# IO.net
KiCad netlist of a schematic drawn in Altium Designer
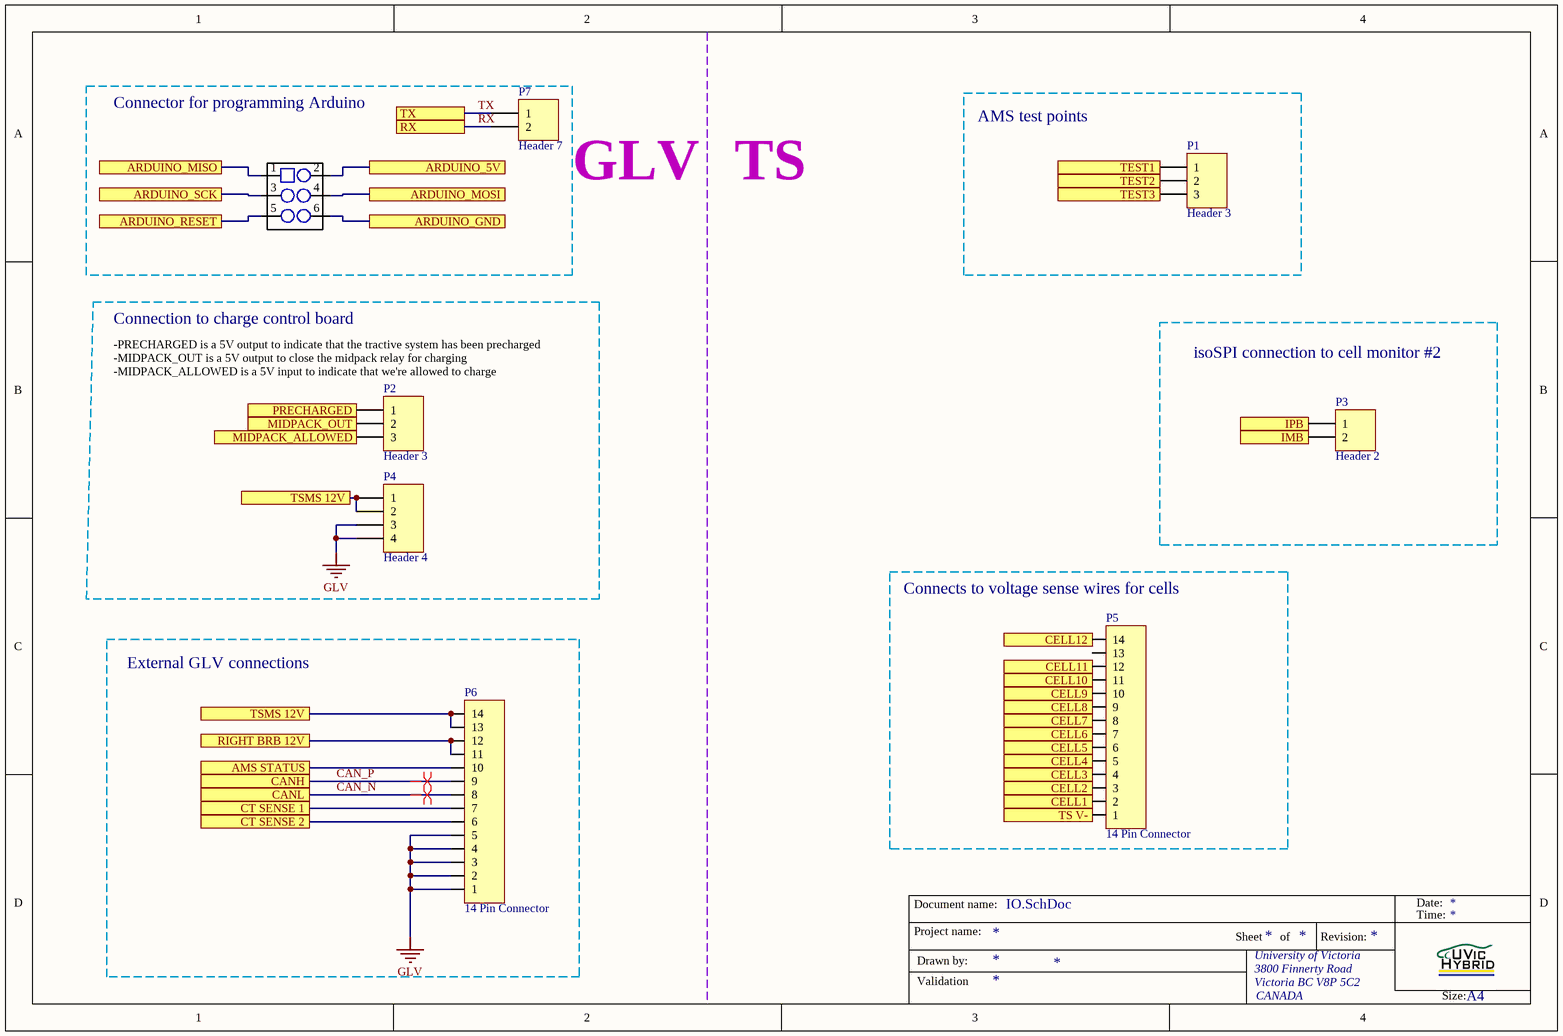
[diagram p0: IO.SchDoc]

(export (version "E")
  (design (tool "Eeschema 10.0.6"))
  (components
    (comp (ref "1")
      (value "ICSP Connector")
      (footprint "ICSP Connector")
      (libsource (lib "AMSComponents") (part "ICSP Connector"))
    )
    (comp (ref "P1")
      (value "Header 3")
      (footprint "3-pin Vertical nanofit")
      (description "Header, 3-Pin")
      (fields (field (name "PUBLISHER") "Altium Limited"))
      (libsource (lib "Miscellaneous Connectors") (part "Header 3"))
    )
    (comp (ref "P2")
      (value "Header 3")
      (footprint "3-pin Vertical nanofit")
      (description "Header, 3-Pin")
      (fields (field (name "PUBLISHER") "Altium Limited"))
      (libsource (lib "Miscellaneous Connectors") (part "Header 3"))
    )
    (comp (ref "P3")
      (value "Header 2")
      (footprint "2 Pin Nanofit")
      (description "Header, 2-Pin")
      (fields (field (name "PUBLISHER") "Altium Limited"))
      (libsource (lib "Miscellaneous Connectors") (part "Header 2"))
    )
    (comp (ref "P4")
      (value "Header 4")
      (footprint "4 Pin Vertical Nanofit")
      (description "Header, 4-Pin")
      (fields (field (name "PUBLISHER") "Altium Limited"))
      (libsource (lib "Miscellaneous Connectors") (part "Header 4"))
    )
    (comp (ref "P5")
      (value "14 Pin Connector")
      (footprint "TE Connectivity 14 Pin")
      (libsource (lib "AMSComponents") (part "14 Pin Connector"))
    )
    (comp (ref "P6")
      (value "14 Pin Connector")
      (footprint "TE Connectivity 14 Pin")
      (libsource (lib "AMSComponents") (part "14 Pin Connector"))
    )
    (comp (ref "P7")
      (value "Header 7")
      (footprint "2 Pin Nanofit")
      (description "Header, 2-Pin")
      (fields (field (name "PUBLISHER") "Altium Limited"))
      (libsource (lib "Miscellaneous Connectors") (part "Header 2"))
    )
  )
  (nets
    (net (code "1") (name "/AMS STATUS") (class "Default")
      (node (ref "P6") (pin "10") (pinfunction "10_10") (pintype "passive"))
    )
    (net (code "2") (name "/ARDUINO_5V") (class "Default")
      (node (ref "1") (pin "2") (pinfunction "2_2") (pintype "passive"))
    )
    (net (code "3") (name "/ARDUINO_GND") (class "Default")
      (node (ref "1") (pin "6") (pinfunction "6_6") (pintype "passive"))
    )
    (net (code "4") (name "/ARDUINO_MISO") (class "Default")
      (node (ref "1") (pin "1") (pinfunction "1_1") (pintype "passive"))
    )
    (net (code "5") (name "/ARDUINO_MOSI") (class "Default")
      (node (ref "1") (pin "4") (pinfunction "4_4") (pintype "passive"))
    )
    (net (code "6") (name "/ARDUINO_RESET") (class "Default")
      (node (ref "1") (pin "5") (pinfunction "5_5") (pintype "passive"))
    )
    (net (code "7") (name "/ARDUINO_SCK") (class "Default")
      (node (ref "1") (pin "3") (pinfunction "3_3") (pintype "passive"))
    )
    (net (code "8") (name "/CAN_N") (class "Default")
      (node (ref "P6") (pin "8") (pinfunction "8_8") (pintype "passive"))
    )
    (net (code "9") (name "/CAN_P") (class "Default")
      (node (ref "P6") (pin "9") (pinfunction "9_9") (pintype "passive"))
    )
    (net (code "10") (name "/CELL1") (class "Default")
      (node (ref "P5") (pin "2") (pinfunction "2_2") (pintype "passive"))
    )
    (net (code "11") (name "/CELL2") (class "Default")
      (node (ref "P5") (pin "3") (pinfunction "3_3") (pintype "passive"))
    )
    (net (code "12") (name "/CELL3") (class "Default")
      (node (ref "P5") (pin "4") (pinfunction "4_4") (pintype "passive"))
    )
    (net (code "13") (name "/CELL4") (class "Default")
      (node (ref "P5") (pin "5") (pinfunction "5_5") (pintype "passive"))
    )
    (net (code "14") (name "/CELL5") (class "Default")
      (node (ref "P5") (pin "6") (pinfunction "6_6") (pintype "passive"))
    )
    (net (code "15") (name "/CELL6") (class "Default")
      (node (ref "P5") (pin "7") (pinfunction "7_7") (pintype "passive"))
    )
    (net (code "16") (name "/CELL7") (class "Default")
      (node (ref "P5") (pin "8") (pinfunction "8_8") (pintype "passive"))
    )
    (net (code "17") (name "/CELL8") (class "Default")
      (node (ref "P5") (pin "9") (pinfunction "9_9") (pintype "passive"))
    )
    (net (code "18") (name "/CELL9") (class "Default")
      (node (ref "P5") (pin "10") (pinfunction "10_10") (pintype "passive"))
    )
    (net (code "19") (name "/CELL10") (class "Default")
      (node (ref "P5") (pin "11") (pinfunction "11_11") (pintype "passive"))
    )
    (net (code "20") (name "/CELL11") (class "Default")
      (node (ref "P5") (pin "12") (pinfunction "12_12") (pintype "passive"))
    )
    (net (code "21") (name "/CELL12") (class "Default")
      (node (ref "P5") (pin "14") (pinfunction "14_14") (pintype "passive"))
    )
    (net (code "22") (name "/CT SENSE 1") (class "Default")
      (node (ref "P6") (pin "7") (pinfunction "7_7") (pintype "passive"))
    )
    (net (code "23") (name "/CT SENSE 2") (class "Default")
      (node (ref "P6") (pin "6") (pinfunction "6_6") (pintype "passive"))
    )
    (net (code "24") (name "/IMB") (class "Default")
      (node (ref "P3") (pin "2") (pinfunction "2_2") (pintype "passive"))
    )
    (net (code "25") (name "/IPB") (class "Default")
      (node (ref "P3") (pin "1") (pinfunction "1_1") (pintype "passive"))
    )
    (net (code "26") (name "/MIDPACK_ALLOWED") (class "Default")
      (node (ref "P2") (pin "3") (pinfunction "3_3") (pintype "passive"))
    )
    (net (code "27") (name "/MIDPACK_OUT") (class "Default")
      (node (ref "P2") (pin "2") (pinfunction "2_2") (pintype "passive"))
    )
    (net (code "28") (name "/PRECHARGED") (class "Default")
      (node (ref "P2") (pin "1") (pinfunction "1_1") (pintype "passive"))
    )
    (net (code "29") (name "/RIGHT BRB 12V") (class "Default")
      (node (ref "P6") (pin "11") (pinfunction "11_11") (pintype "passive"))
      (node (ref "P6") (pin "12") (pinfunction "12_12") (pintype "passive"))
    )
    (net (code "30") (name "/RX") (class "Default")
      (node (ref "P7") (pin "2") (pinfunction "2_2") (pintype "passive"))
    )
    (net (code "31") (name "/TEST1") (class "Default")
      (node (ref "P1") (pin "1") (pinfunction "1_1") (pintype "passive"))
    )
    (net (code "32") (name "/TEST2") (class "Default")
      (node (ref "P1") (pin "2") (pinfunction "2_2") (pintype "passive"))
    )
    (net (code "33") (name "/TEST3") (class "Default")
      (node (ref "P1") (pin "3") (pinfunction "3_3") (pintype "passive"))
    )
    (net (code "34") (name "/TS V-") (class "Default")
      (node (ref "P5") (pin "1") (pinfunction "1_1") (pintype "passive"))
    )
    (net (code "35") (name "/TSMS 12V") (class "Default")
      (node (ref "P4") (pin "1") (pinfunction "1_1") (pintype "passive"))
      (node (ref "P4") (pin "2") (pinfunction "2_2") (pintype "passive"))
      (node (ref "P6") (pin "13") (pinfunction "13_13") (pintype "passive"))
      (node (ref "P6") (pin "14") (pinfunction "14_14") (pintype "passive"))
    )
    (net (code "36") (name "/TX") (class "Default")
      (node (ref "P7") (pin "1") (pinfunction "1_1") (pintype "passive"))
    )
    (net (code "37") (name "GLV") (class "Default")
      (node (ref "P4") (pin "3") (pinfunction "3_3") (pintype "passive"))
      (node (ref "P4") (pin "4") (pinfunction "4_4") (pintype "passive"))
      (node (ref "P6") (pin "1") (pinfunction "1_1") (pintype "passive"))
      (node (ref "P6") (pin "2") (pinfunction "2_2") (pintype "passive"))
      (node (ref "P6") (pin "3") (pinfunction "3_3") (pintype "passive"))
      (node (ref "P6") (pin "4") (pinfunction "4_4") (pintype "passive"))
      (node (ref "P6") (pin "5") (pinfunction "5_5") (pintype "passive"))
    )
    (net (code "38") (name "unconnected-(P5-Pad13)") (class "Default")
      (node (ref "P5") (pin "13") (pinfunction "13_13") (pintype "passive"))
    )
  )
)
